# V1_0.net
KiCad netlist of a schematic drawn in Altium Designer
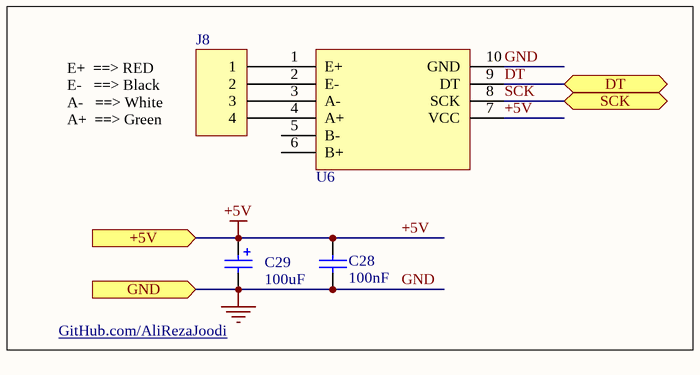
[diagram p0: V1.0.SchDoc]

(export (version "E")
  (design (tool "Eeschema 10.0.6"))
  (components
    (comp (ref "C28")
      (value "100nF")
      (footprint "CAPNTO2.54-3.05x1.78A")
      (description "Capacitor")
      (fields (field (name "MANUFACTURER") "Generic Components") (field (name "PUBLISHER") "Altium Limited"))
      (libsource (lib "Miscellaneous Devices") (part "Cap"))
    )
    (comp (ref "C29")
      (value "100uF")
      (footprint "CAPPR2.5-6.3x5")
      (description "Polarized Capacitor (Radial)")
      (fields (field (name "MANUFACTURER") "Generic Components") (field (name "PUBLISHER") "Altium Limited"))
      (libsource (lib "Miscellaneous Devices") (part "Cap Pol1"))
    )
    (comp (ref "J8")
      (value "4Pin")
      (footprint "Fonics_4PIN_1")
      (description "Header, 4-Pin")
      (fields (field (name "MANUFACTURER") "Generic Components") (field (name "PUBLISHER") "Altium Limited"))
      (libsource (lib "Miscellaneous Connectors") (part "Header 4"))
    )
    (comp (ref "U6")
      (value "HX711")
      (footprint "HX711")
      (description "Header, 6-Pin")
      (fields (field (name "MANUFACTURER") "Generic Components") (field (name "PUBLISHER") "Altium Limited"))
      (libsource (lib "my Libraries") (part "HX711"))
    )
  )
  (nets
    (net (code "1") (name "+5V") (class "Default")
      (node (ref "C28") (pin "2") (pinfunction "2_2") (pintype "passive"))
      (node (ref "C29") (pin "1") (pinfunction "1_1") (pintype "passive"))
      (node (ref "U6") (pin "7") (pinfunction "VCC_7") (pintype "passive"))
    )
    (net (code "2") (name "/DT") (class "Default")
      (node (ref "U6") (pin "9") (pinfunction "DT_9") (pintype "passive"))
    )
    (net (code "3") (name "/SCK") (class "Default")
      (node (ref "U6") (pin "8") (pinfunction "SCK_8") (pintype "passive"))
    )
    (net (code "4") (name "GND") (class "Default")
      (node (ref "C28") (pin "1") (pinfunction "1_1") (pintype "passive"))
      (node (ref "C29") (pin "2") (pinfunction "2_2") (pintype "passive"))
      (node (ref "U6") (pin "10") (pinfunction "GND_10") (pintype "passive"))
    )
    (net (code "5") (name "Net-(U6-A+)") (class "Default")
      (node (ref "J8") (pin "4") (pinfunction "4_4") (pintype "passive"))
      (node (ref "U6") (pin "4") (pinfunction "A+_4") (pintype "passive"))
    )
    (net (code "6") (name "Net-(U6-A-)") (class "Default")
      (node (ref "J8") (pin "3") (pinfunction "3_3") (pintype "passive"))
      (node (ref "U6") (pin "3") (pinfunction "A-_3") (pintype "passive"))
    )
    (net (code "7") (name "Net-(U6-E+)") (class "Default")
      (node (ref "J8") (pin "1") (pinfunction "1_1") (pintype "passive"))
      (node (ref "U6") (pin "1") (pinfunction "E+_1") (pintype "passive"))
    )
    (net (code "8") (name "Net-(U6-E-)") (class "Default")
      (node (ref "J8") (pin "2") (pinfunction "2_2") (pintype "passive"))
      (node (ref "U6") (pin "2") (pinfunction "E-_2") (pintype "passive"))
    )
    (net (code "9") (name "unconnected-(U6-B+-Pad6)") (class "Default")
      (node (ref "U6") (pin "6") (pinfunction "B+_6") (pintype "passive"))
    )
    (net (code "10") (name "unconnected-(U6-B--Pad5)") (class "Default")
      (node (ref "U6") (pin "5") (pinfunction "B-_5") (pintype "passive"))
    )
  )
)
